# eeprom_shield.net
KiCad netlist of a schematic drawn in EAGLE
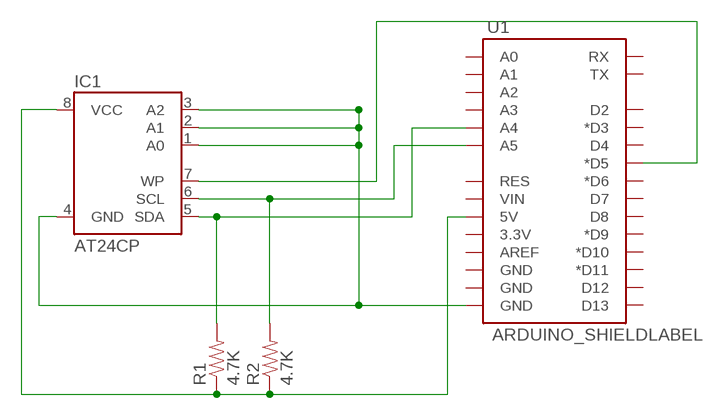
[diagram p0: schematic, sheet 1]

(export (version "E")
  (design (tool "Eeschema 10.0.6"))
  (components
    (comp (ref "IC1")
      (value "AT24CP")
      (footprint "eagle-import:DIL08")
      (fields (field (name "MPN") "AT24C1024BW-SH-B"))
      (libsource (lib "eagle-import") (part "AT24CP"))
    )
    (comp (ref "R1")
      (value "4.7K")
      (footprint "eagle-import:AXIAL-0.4")
      (libsource (lib "eagle-import") (part "RESISTORPTH-1/4W"))
    )
    (comp (ref "R2")
      (value "4.7K")
      (footprint "eagle-import:AXIAL-0.4")
      (libsource (lib "eagle-import") (part "RESISTORPTH-1/4W"))
    )
    (comp (ref "U1")
      (value "ARDUINO_SHIELDLABEL")
      (footprint "eagle-import:DUEMILANOVE_SHIELD")
      (libsource (lib "eagle-import") (part "ARDUINO_SHIELDLABEL"))
    )
  )
  (nets
    (net (code "1") (name "Net-(IC1-A0)") (class "Default")
      (node (ref "IC1") (pin "1") (pinfunction "A0_1") (pintype "input"))
      (node (ref "IC1") (pin "2") (pinfunction "A1_2") (pintype "input"))
      (node (ref "IC1") (pin "3") (pinfunction "A2_3") (pintype "input"))
      (node (ref "IC1") (pin "4") (pinfunction "GND_4") (pintype "power_in"))
      (node (ref "U1") (pin "GND@0") (pinfunction "GND_GND@0") (pintype "bidirectional"))
    )
    (net (code "2") (name "Net-(IC1-SCL)") (class "Default")
      (node (ref "IC1") (pin "6") (pinfunction "SCL_6") (pintype "bidirectional"))
      (node (ref "R2") (pin "P$2") (pinfunction "2_P$2") (pintype "passive"))
      (node (ref "U1") (pin "A5") (pinfunction "A5_A5") (pintype "bidirectional"))
    )
    (net (code "3") (name "Net-(IC1-SDA)") (class "Default")
      (node (ref "IC1") (pin "5") (pinfunction "SDA_5") (pintype "bidirectional"))
      (node (ref "R1") (pin "P$2") (pinfunction "2_P$2") (pintype "passive"))
      (node (ref "U1") (pin "A4") (pinfunction "A4_A4") (pintype "bidirectional"))
    )
    (net (code "4") (name "Net-(IC1-VCC)") (class "Default")
      (node (ref "IC1") (pin "8") (pinfunction "VCC_8") (pintype "power_in"))
      (node (ref "R1") (pin "P$1") (pinfunction "1_P$1") (pintype "passive"))
      (node (ref "R2") (pin "P$1") (pinfunction "1_P$1") (pintype "passive"))
      (node (ref "U1") (pin "5V") (pinfunction "5V_5V") (pintype "bidirectional"))
    )
    (net (code "5") (name "Net-(IC1-WP)") (class "Default")
      (node (ref "IC1") (pin "7") (pinfunction "WP_7") (pintype "input"))
      (node (ref "U1") (pin "D5") (pinfunction "*D5_D5") (pintype "bidirectional"))
    )
    (net (code "6") (name "unconnected-(U1-*D3-PadD3)") (class "Default")
      (node (ref "U1") (pin "D3") (pinfunction "*D3_D3") (pintype "bidirectional"))
    )
    (net (code "7") (name "unconnected-(U1-*D6-PadD6)") (class "Default")
      (node (ref "U1") (pin "D6") (pinfunction "*D6_D6") (pintype "bidirectional"))
    )
    (net (code "8") (name "unconnected-(U1-*D9-PadD9)") (class "Default")
      (node (ref "U1") (pin "D9") (pinfunction "*D9_D9") (pintype "bidirectional"))
    )
    (net (code "9") (name "unconnected-(U1-*D10-PadD10)") (class "Default")
      (node (ref "U1") (pin "D10") (pinfunction "*D10_D10") (pintype "bidirectional"))
    )
    (net (code "10") (name "unconnected-(U1-*D11-PadD11)") (class "Default")
      (node (ref "U1") (pin "D11") (pinfunction "*D11_D11") (pintype "bidirectional"))
    )
    (net (code "11") (name "unconnected-(U1-GND-PadGND@1)") (class "Default")
      (node (ref "U1") (pin "GND@1") (pinfunction "GND_GND@1") (pintype "bidirectional"))
    )
    (net (code "12") (name "unconnected-(U1-GND-PadGND@2)") (class "Default")
      (node (ref "U1") (pin "GND@2") (pinfunction "GND_GND@2") (pintype "bidirectional"))
    )
    (net (code "13") (name "unconnected-(U1-Pad3.3V)") (class "Default")
      (node (ref "U1") (pin "3.3V") (pinfunction "3.3V_3.3V") (pintype "bidirectional"))
    )
    (net (code "14") (name "unconnected-(U1-PadA0)") (class "Default")
      (node (ref "U1") (pin "A0") (pinfunction "A0_A0") (pintype "bidirectional"))
    )
    (net (code "15") (name "unconnected-(U1-PadA1)") (class "Default")
      (node (ref "U1") (pin "A1") (pinfunction "A1_A1") (pintype "bidirectional"))
    )
    (net (code "16") (name "unconnected-(U1-PadA2)") (class "Default")
      (node (ref "U1") (pin "A2") (pinfunction "A2_A2") (pintype "bidirectional"))
    )
    (net (code "17") (name "unconnected-(U1-PadA3)") (class "Default")
      (node (ref "U1") (pin "A3") (pinfunction "A3_A3") (pintype "bidirectional"))
    )
    (net (code "18") (name "unconnected-(U1-PadAREF)") (class "Default")
      (node (ref "U1") (pin "AREF") (pinfunction "AREF_AREF") (pintype "bidirectional"))
    )
    (net (code "19") (name "unconnected-(U1-PadD2)") (class "Default")
      (node (ref "U1") (pin "D2") (pinfunction "D2_D2") (pintype "bidirectional"))
    )
    (net (code "20") (name "unconnected-(U1-PadD4)") (class "Default")
      (node (ref "U1") (pin "D4") (pinfunction "D4_D4") (pintype "bidirectional"))
    )
    (net (code "21") (name "unconnected-(U1-PadD7)") (class "Default")
      (node (ref "U1") (pin "D7") (pinfunction "D7_D7") (pintype "bidirectional"))
    )
    (net (code "22") (name "unconnected-(U1-PadD8)") (class "Default")
      (node (ref "U1") (pin "D8") (pinfunction "D8_D8") (pintype "bidirectional"))
    )
    (net (code "23") (name "unconnected-(U1-PadD12)") (class "Default")
      (node (ref "U1") (pin "D12") (pinfunction "D12_D12") (pintype "bidirectional"))
    )
    (net (code "24") (name "unconnected-(U1-PadD13)") (class "Default")
      (node (ref "U1") (pin "D13") (pinfunction "D13_D13") (pintype "bidirectional"))
    )
    (net (code "25") (name "unconnected-(U1-PadRES)") (class "Default")
      (node (ref "U1") (pin "RES") (pinfunction "RES_RES") (pintype "bidirectional"))
    )
    (net (code "26") (name "unconnected-(U1-PadRX)") (class "Default")
      (node (ref "U1") (pin "RX") (pinfunction "RX_RX") (pintype "bidirectional"))
    )
    (net (code "27") (name "unconnected-(U1-PadTX)") (class "Default")
      (node (ref "U1") (pin "TX") (pinfunction "TX_TX") (pintype "bidirectional"))
    )
    (net (code "28") (name "unconnected-(U1-PadVIN)") (class "Default")
      (node (ref "U1") (pin "VIN") (pinfunction "VIN_VIN") (pintype "bidirectional"))
    )
  )
)
